# MAIN.net
KiCad netlist of a schematic drawn in Altium Designer
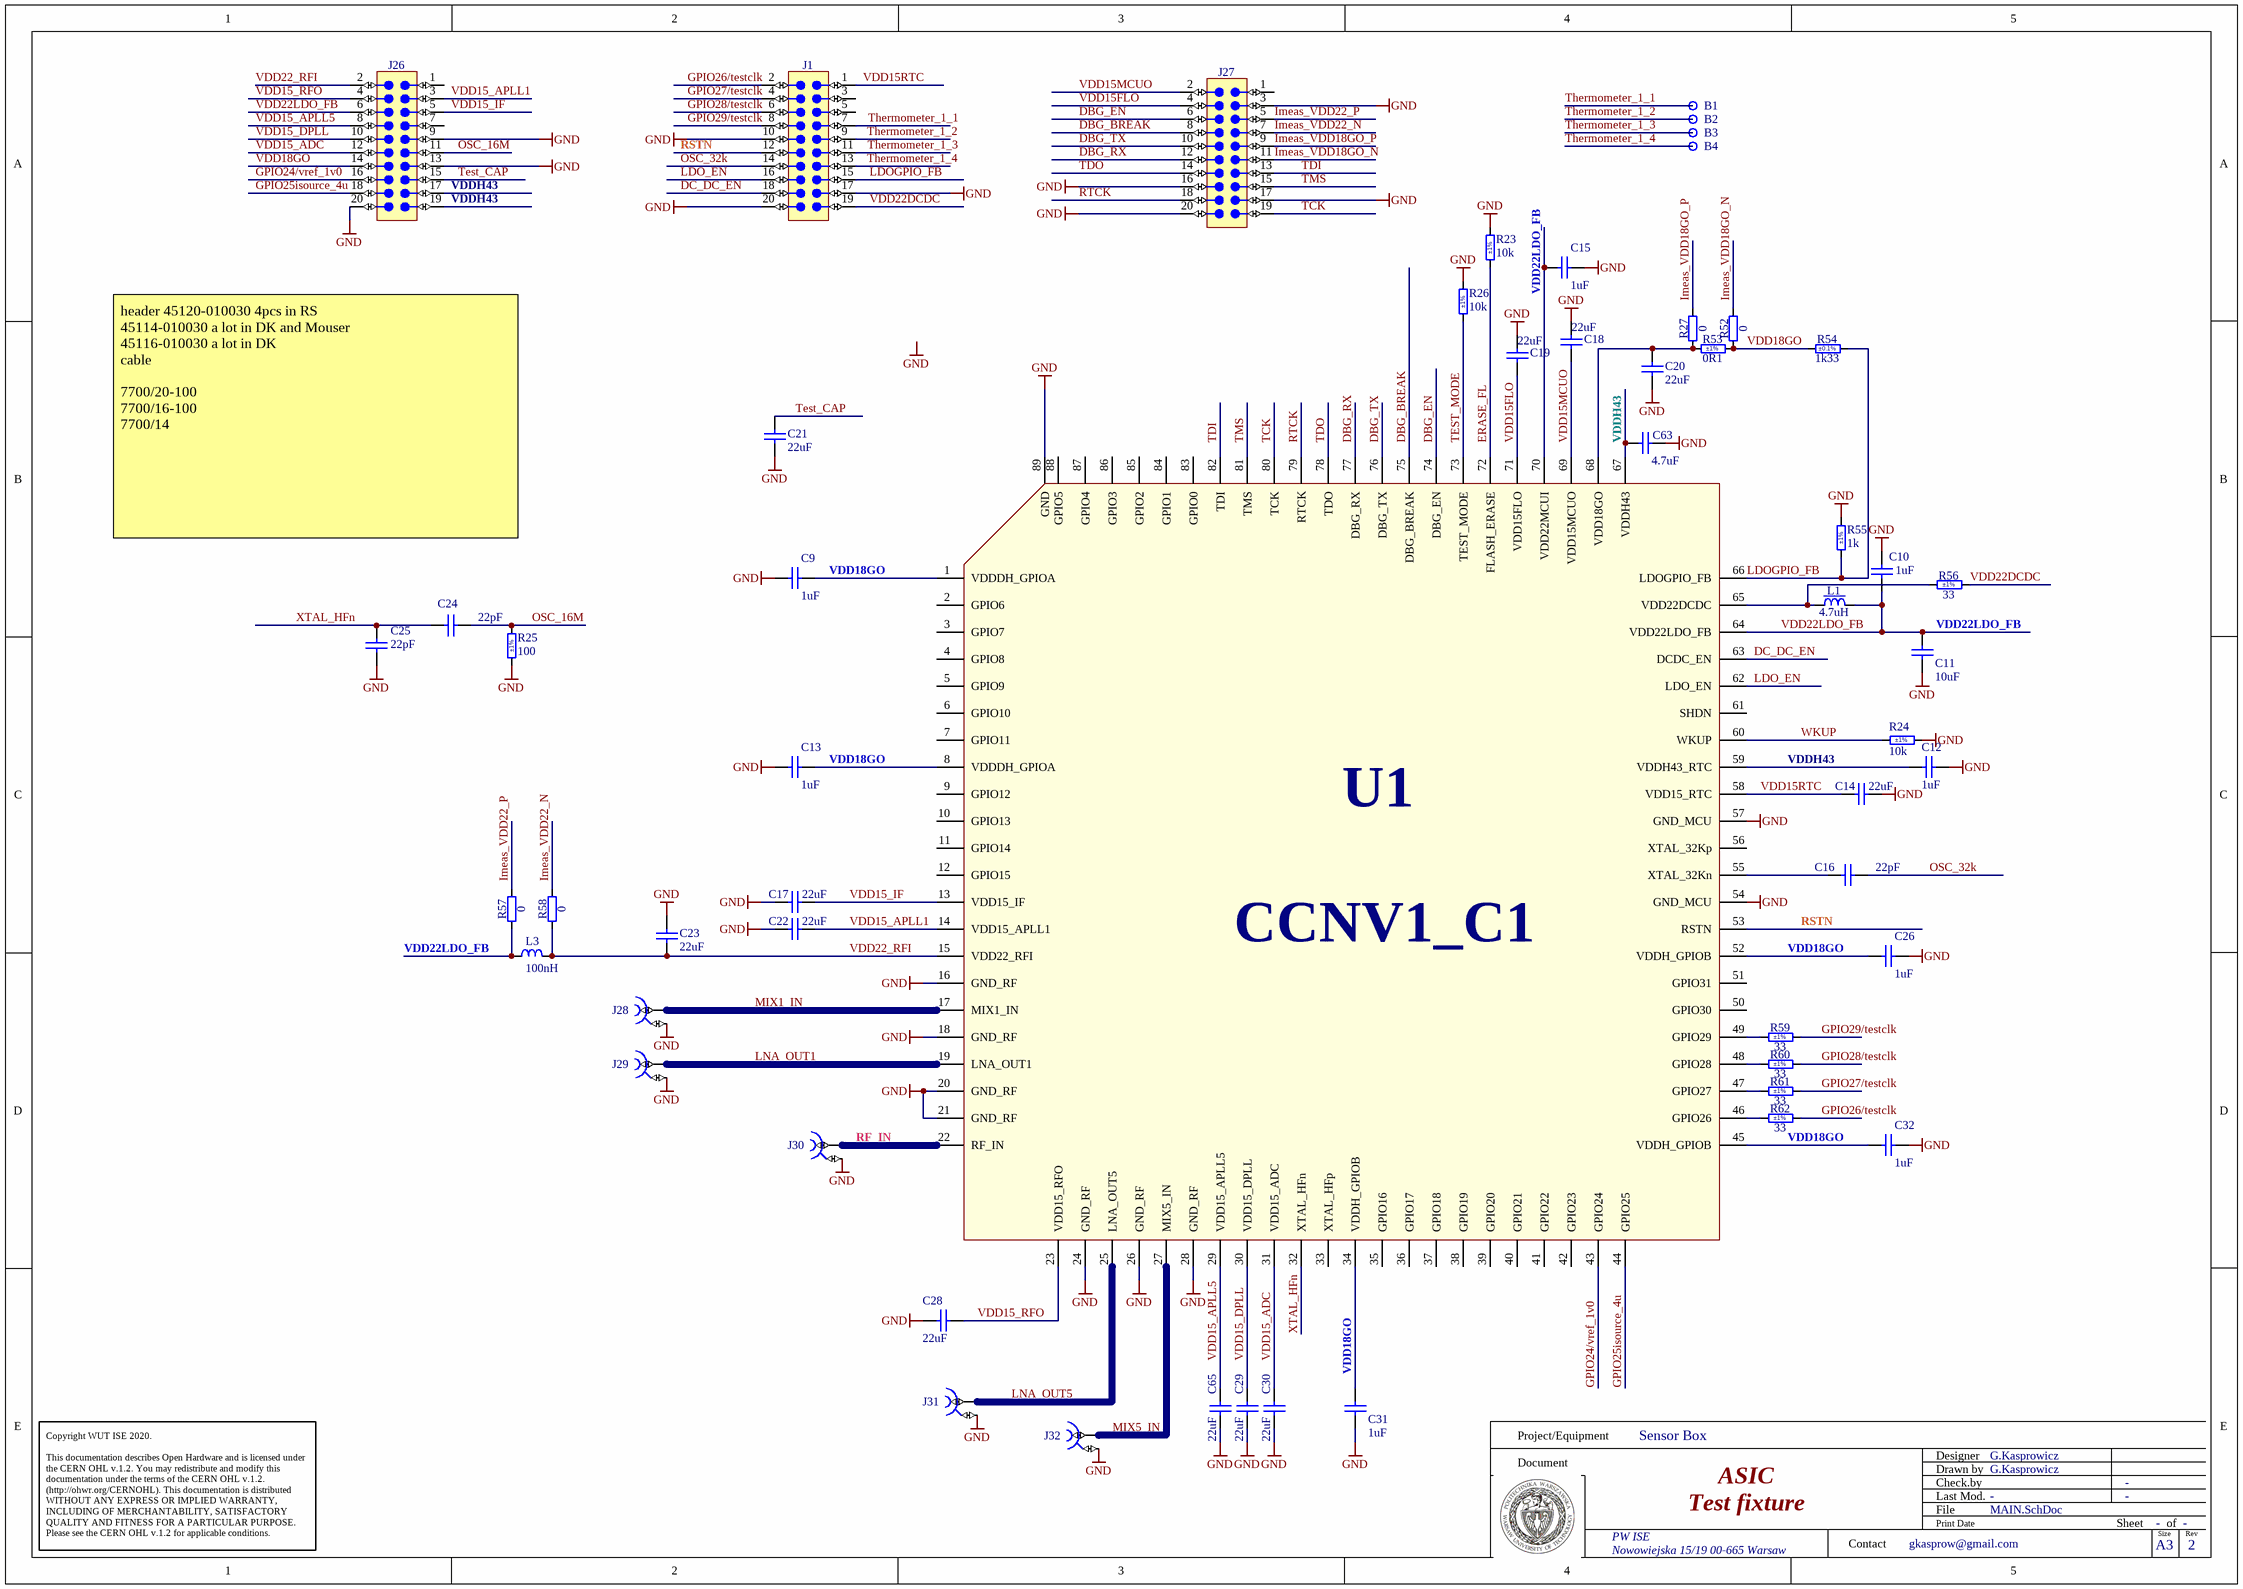
[diagram p0: MAIN.SchDoc]

(export (version "E")
  (design (tool "Eeschema 10.0.6"))
  (components
    (comp (ref "B1")
      (value "Plated Hole")
      (footprint "c100h50")
      (description "Single Terminal Socket")
      (fields (field (name "PART NUMBER") "PLATED_HOLE0.5_PAD1.0") (field (name "AUTHOR") "CERN DEM JMW"))
      (libsource (lib "Eletro-mechanical") (part "Single Terminal Socket"))
    )
    (comp (ref "B2")
      (value "Plated Hole")
      (footprint "c100h50")
      (description "Single Terminal Socket")
      (fields (field (name "PART NUMBER") "PLATED_HOLE0.5_PAD1.0") (field (name "AUTHOR") "CERN DEM JMW"))
      (libsource (lib "Eletro-mechanical") (part "Single Terminal Socket"))
    )
    (comp (ref "B3")
      (value "Plated Hole")
      (footprint "c100h50")
      (description "Single Terminal Socket")
      (fields (field (name "PART NUMBER") "PLATED_HOLE0.5_PAD1.0") (field (name "AUTHOR") "CERN DEM JMW"))
      (libsource (lib "Eletro-mechanical") (part "Single Terminal Socket"))
    )
    (comp (ref "B4")
      (value "Plated Hole")
      (footprint "c100h50")
      (description "Single Terminal Socket")
      (fields (field (name "PART NUMBER") "PLATED_HOLE0.5_PAD1.0") (field (name "AUTHOR") "CERN DEM JMW"))
      (libsource (lib "Eletro-mechanical") (part "Single Terminal Socket"))
    )
    (comp (ref "C9")
      (value "1uF")
      (footprint "CAPC1005X55N")
      (description "Non-polarised capacitor")
      (fields
        (field (name "PART NUMBER") "CC0402_1UF_16V_10%_X5R")
        (field (name "VOLTAGE") "16V")
        (field (name "AUTHOR") "CERN DEM JLC")
      )
      (libsource (lib "Capacitors") (part "Capacitor - non polarized"))
    )
    (comp (ref "C10")
      (value "1uF")
      (footprint "CAPC1005X55N")
      (description "Non-polarised capacitor")
      (fields
        (field (name "PART NUMBER") "CC0402_1UF_16V_10%_X5R")
        (field (name "VOLTAGE") "16V")
        (field (name "AUTHOR") "CERN DEM JLC")
      )
      (libsource (lib "Capacitors") (part "Capacitor - non polarized"))
    )
    (comp (ref "C11")
      (value "10uF")
      (footprint "CAPC1608X80N")
      (description "Non-polarised capacitor")
      (fields
        (field (name "PART NUMBER") "CC0603_10UF_10V_10%_X5R")
        (field (name "VOLTAGE") "10V")
        (field (name "AUTHOR") "CERN DEM JLC")
      )
      (libsource (lib "Capacitors") (part "Capacitor - non polarized"))
    )
    (comp (ref "C12")
      (value "1uF")
      (footprint "CAPC1005X55N")
      (description "Non-polarised capacitor")
      (fields
        (field (name "PART NUMBER") "CC0402_1UF_16V_10%_X5R")
        (field (name "VOLTAGE") "16V")
        (field (name "AUTHOR") "CERN DEM JLC")
      )
      (libsource (lib "Capacitors") (part "Capacitor - non polarized"))
    )
    (comp (ref "C13")
      (value "1uF")
      (footprint "CAPC1005X55N")
      (description "Non-polarised capacitor")
      (fields
        (field (name "PART NUMBER") "CC0402_1UF_16V_10%_X5R")
        (field (name "VOLTAGE") "16V")
        (field (name "AUTHOR") "CERN DEM JLC")
      )
      (libsource (lib "Capacitors") (part "Capacitor - non polarized"))
    )
    (comp (ref "C14")
      (value "22uF")
      (footprint "CAPC1608X90N")
      (description "Non-polarised capacitor")
      (fields
        (field (name "PART NUMBER") "CC0603_22UF_10V_20%_X5R")
        (field (name "VOLTAGE") "10V")
        (field (name "AUTHOR") "CERN DEM BC")
      )
      (libsource (lib "Capacitors") (part "Capacitor - non polarized"))
    )
    (comp (ref "C15")
      (value "1uF")
      (footprint "CAPC1005X55N")
      (description "Non-polarised capacitor")
      (fields
        (field (name "PART NUMBER") "CC0402_1UF_16V_10%_X5R")
        (field (name "VOLTAGE") "16V")
        (field (name "AUTHOR") "CERN DEM JLC")
      )
      (libsource (lib "Capacitors") (part "Capacitor - non polarized"))
    )
    (comp (ref "C16")
      (value "22pF")
      (footprint "CAPC1005X55N")
      (description "Non-polarised capacitor")
      (fields
        (field (name "PART NUMBER") "CC0402_22PF_50V_5%_C0G")
        (field (name "VOLTAGE") "50V")
        (field (name "AUTHOR") "CERN DEM JLC")
      )
      (libsource (lib "Capacitors") (part "Capacitor - non polarized"))
    )
    (comp (ref "C17")
      (value "22uF")
      (footprint "CAPC1608X90N")
      (description "Non-polarised capacitor")
      (fields
        (field (name "PART NUMBER") "CC0603_22UF_10V_20%_X5R")
        (field (name "VOLTAGE") "10V")
        (field (name "AUTHOR") "CERN DEM BC")
      )
      (libsource (lib "Capacitors") (part "Capacitor - non polarized"))
    )
    (comp (ref "C18")
      (value "22uF")
      (footprint "CAPC1608X90N")
      (description "Non-polarised capacitor")
      (fields
        (field (name "PART NUMBER") "CC0603_22UF_10V_20%_X5R")
        (field (name "VOLTAGE") "10V")
        (field (name "AUTHOR") "CERN DEM BC")
      )
      (libsource (lib "Capacitors") (part "Capacitor - non polarized"))
    )
    (comp (ref "C19")
      (value "22uF")
      (footprint "CAPC1608X90N")
      (description "Non-polarised capacitor")
      (fields
        (field (name "PART NUMBER") "CC0603_22UF_10V_20%_X5R")
        (field (name "VOLTAGE") "10V")
        (field (name "AUTHOR") "CERN DEM BC")
      )
      (libsource (lib "Capacitors") (part "Capacitor - non polarized"))
    )
    (comp (ref "C20")
      (value "22uF")
      (footprint "CAPC1608X90N")
      (description "Non-polarised capacitor")
      (fields
        (field (name "PART NUMBER") "CC0603_22UF_10V_20%_X5R")
        (field (name "VOLTAGE") "10V")
        (field (name "AUTHOR") "CERN DEM BC")
      )
      (libsource (lib "Capacitors") (part "Capacitor - non polarized"))
    )
    (comp (ref "C21")
      (value "22uF")
      (footprint "CAPC1608X90N")
      (description "Non-polarised capacitor")
      (fields
        (field (name "PART NUMBER") "CC0603_22UF_10V_20%_X5R")
        (field (name "VOLTAGE") "10V")
        (field (name "AUTHOR") "CERN DEM BC")
      )
      (libsource (lib "Capacitors") (part "Capacitor - non polarized"))
    )
    (comp (ref "C22")
      (value "22uF")
      (footprint "CAPC1608X90N")
      (description "Non-polarised capacitor")
      (fields
        (field (name "PART NUMBER") "CC0603_22UF_10V_20%_X5R")
        (field (name "VOLTAGE") "10V")
        (field (name "AUTHOR") "CERN DEM BC")
      )
      (libsource (lib "Capacitors") (part "Capacitor - non polarized"))
    )
    (comp (ref "C23")
      (value "22uF")
      (footprint "CAPC1608X90N")
      (description "Non-polarised capacitor")
      (fields
        (field (name "PART NUMBER") "CC0603_22UF_10V_20%_X5R")
        (field (name "VOLTAGE") "10V")
        (field (name "AUTHOR") "CERN DEM BC")
      )
      (libsource (lib "Capacitors") (part "Capacitor - non polarized"))
    )
    (comp (ref "C24")
      (value "22pF")
      (footprint "CAPC1005X55N")
      (description "Non-polarised capacitor")
      (fields
        (field (name "PART NUMBER") "CC0402_22PF_50V_5%_C0G")
        (field (name "VOLTAGE") "50V")
        (field (name "AUTHOR") "CERN DEM JLC")
      )
      (libsource (lib "Capacitors") (part "Capacitor - non polarized"))
    )
    (comp (ref "C25")
      (value "22pF")
      (footprint "CAPC1005X55N")
      (description "Non-polarised capacitor")
      (fields
        (field (name "PART NUMBER") "CC0402_22PF_50V_5%_C0G")
        (field (name "VOLTAGE") "50V")
        (field (name "AUTHOR") "CERN DEM JLC")
      )
      (libsource (lib "Capacitors") (part "Capacitor - non polarized"))
    )
    (comp (ref "C26")
      (value "1uF")
      (footprint "CAPC1005X55N")
      (description "Non-polarised capacitor")
      (fields
        (field (name "PART NUMBER") "CC0402_1UF_16V_10%_X5R")
        (field (name "VOLTAGE") "16V")
        (field (name "AUTHOR") "CERN DEM JLC")
      )
      (libsource (lib "Capacitors") (part "Capacitor - non polarized"))
    )
    (comp (ref "C28")
      (value "22uF")
      (footprint "CAPC1608X90N")
      (description "Non-polarised capacitor")
      (fields
        (field (name "PART NUMBER") "CC0603_22UF_10V_20%_X5R")
        (field (name "VOLTAGE") "10V")
        (field (name "AUTHOR") "CERN DEM BC")
      )
      (libsource (lib "Capacitors") (part "Capacitor - non polarized"))
    )
    (comp (ref "C29")
      (value "22uF")
      (footprint "CAPC1608X90N")
      (description "Non-polarised capacitor")
      (fields
        (field (name "PART NUMBER") "CC0603_22UF_10V_20%_X5R")
        (field (name "VOLTAGE") "10V")
        (field (name "AUTHOR") "CERN DEM BC")
      )
      (libsource (lib "Capacitors") (part "Capacitor - non polarized"))
    )
    (comp (ref "C30")
      (value "22uF")
      (footprint "CAPC1608X90N")
      (description "Non-polarised capacitor")
      (fields
        (field (name "PART NUMBER") "CC0603_22UF_10V_20%_X5R")
        (field (name "VOLTAGE") "10V")
        (field (name "AUTHOR") "CERN DEM BC")
      )
      (libsource (lib "Capacitors") (part "Capacitor - non polarized"))
    )
    (comp (ref "C31")
      (value "1uF")
      (footprint "CAPC1005X55N")
      (description "Non-polarised capacitor")
      (fields
        (field (name "PART NUMBER") "CC0402_1UF_16V_10%_X5R")
        (field (name "VOLTAGE") "16V")
        (field (name "AUTHOR") "CERN DEM JLC")
      )
      (libsource (lib "Capacitors") (part "Capacitor - non polarized"))
    )
    (comp (ref "C32")
      (value "1uF")
      (footprint "CAPC1005X55N")
      (description "Non-polarised capacitor")
      (fields
        (field (name "PART NUMBER") "CC0402_1UF_16V_10%_X5R")
        (field (name "VOLTAGE") "16V")
        (field (name "AUTHOR") "CERN DEM JLC")
      )
      (libsource (lib "Capacitors") (part "Capacitor - non polarized"))
    )
    (comp (ref "C63")
      (value "4.7uF")
      (footprint "CAPC1005X55N")
      (description "Non-polarised capacitor")
      (fields
        (field (name "PART NUMBER") "CC0402_4.7UF_10V_10%_X5R")
        (field (name "VOLTAGE") "10V")
        (field (name "AUTHOR") "CERN DEM BC")
      )
      (libsource (lib "Capacitors") (part "Capacitor - non polarized"))
    )
    (comp (ref "C65")
      (value "22uF")
      (footprint "CAPC1608X90N")
      (description "Non-polarised capacitor")
      (fields
        (field (name "PART NUMBER") "CC0603_22UF_10V_20%_X5R")
        (field (name "VOLTAGE") "10V")
        (field (name "AUTHOR") "CERN DEM BC")
      )
      (libsource (lib "Capacitors") (part "Capacitor - non polarized"))
    )
    (comp (ref "J1")
      (value "Header 20")
      (footprint "3M_45220-600230")
      (description "Connector 20 Male")
      (fields
        (field (name "PART NUMBER") "3M_45220-600230")
        (field (name "MANUFACTURER") "3M")
        (field (name "AUTHOR") "CERN DEM MR")
      )
      (libsource (lib "Connectors") (part "Connector 20 Male"))
    )
    (comp (ref "J26")
      (value "Header 20")
      (footprint "3M_45220-600230")
      (description "Connector 20 Male")
      (fields
        (field (name "PART NUMBER") "3M_45220-600230")
        (field (name "MANUFACTURER") "3M")
        (field (name "AUTHOR") "CERN DEM MR")
      )
      (libsource (lib "Connectors") (part "Connector 20 Male"))
    )
    (comp (ref "J27")
      (value "Header 20")
      (footprint "3M_45220-600230")
      (description "Connector 20 Male")
      (fields
        (field (name "PART NUMBER") "3M_45220-600230")
        (field (name "MANUFACTURER") "3M")
        (field (name "AUTHOR") "CERN DEM MR")
      )
      (libsource (lib "Connectors") (part "Connector 20 Male"))
    )
    (comp (ref "J28")
      (value "Coax_1Female_1Shield")
      (footprint "SAMTEC_MMCX-J-P-H-ST-TH1")
      (fields
        (field (name "PART NUMBER") "SAMTEC_MMCX-J-P-H-ST-TH1")
        (field (name "MANUFACTURER") "SAMTEC")
        (field (name "MANUFACTURER PART NUMBER") "MMCX-J-P-H-ST-TH1")
        (field (name "AUTHOR") "CERN DEM JLC")
      )
      (libsource (lib "Connectors") (part "Coax_1Female_1Shield"))
    )
    (comp (ref "J29")
      (value "Coax_1Female_1Shield")
      (footprint "SAMTEC_MMCX-J-P-H-ST-TH1")
      (fields
        (field (name "PART NUMBER") "SAMTEC_MMCX-J-P-H-ST-TH1")
        (field (name "MANUFACTURER") "SAMTEC")
        (field (name "MANUFACTURER PART NUMBER") "MMCX-J-P-H-ST-TH1")
        (field (name "AUTHOR") "CERN DEM JLC")
      )
      (libsource (lib "Connectors") (part "Coax_1Female_1Shield"))
    )
    (comp (ref "J30")
      (value "Coax_1Female_1Shield")
      (footprint "SAMTEC_MMCX-J-P-H-ST-TH1")
      (fields
        (field (name "PART NUMBER") "SAMTEC_MMCX-J-P-H-ST-TH1")
        (field (name "MANUFACTURER") "SAMTEC")
        (field (name "MANUFACTURER PART NUMBER") "MMCX-J-P-H-ST-TH1")
        (field (name "AUTHOR") "CERN DEM JLC")
      )
      (libsource (lib "Connectors") (part "Coax_1Female_1Shield"))
    )
    (comp (ref "J31")
      (value "Coax_1Female_1Shield")
      (footprint "SAMTEC_MMCX-J-P-H-ST-TH1")
      (fields
        (field (name "PART NUMBER") "SAMTEC_MMCX-J-P-H-ST-TH1")
        (field (name "MANUFACTURER") "SAMTEC")
        (field (name "MANUFACTURER PART NUMBER") "MMCX-J-P-H-ST-TH1")
        (field (name "AUTHOR") "CERN DEM JLC")
      )
      (libsource (lib "Connectors") (part "Coax_1Female_1Shield"))
    )
    (comp (ref "J32")
      (value "Coax_1Female_1Shield")
      (footprint "SAMTEC_MMCX-J-P-H-ST-TH1")
      (fields
        (field (name "PART NUMBER") "SAMTEC_MMCX-J-P-H-ST-TH1")
        (field (name "MANUFACTURER") "SAMTEC")
        (field (name "MANUFACTURER PART NUMBER") "MMCX-J-P-H-ST-TH1")
        (field (name "AUTHOR") "CERN DEM JLC")
      )
      (libsource (lib "Connectors") (part "Coax_1Female_1Shield"))
    )
    (comp (ref "L1")
      (value "4.7uH")
      (footprint "INDC2012X145N")
      (description "Inductor With Core")
      (fields
        (field (name "PART NUMBER") "IND0805_4.7UH_20%_KEMET_L-DWI")
        (field (name "POWER") "360mA")
        (field (name "AUTHOR") "CERN DEM JLC")
      )
      (libsource (lib "Inductors & Transformers") (part "Inductor With Magnetic core"))
    )
    (comp (ref "L3")
      (value "100nH")
      (footprint "INDC1005X55N")
      (description "Inductor")
      (fields
        (field (name "PART NUMBER") "IND0402_100NH_5%_TDK_MLJ1005")
        (field (name "POWER") "400mA")
        (field (name "AUTHOR") "CERN DEM BC")
      )
      (libsource (lib "Inductors & Transformers") (part "Inductor"))
    )
    (comp (ref "R23")
      (value "10k")
      (footprint "RESC1005X40N")
      (description "Resistor - 1%")
      (fields
        (field (name "TOLERANCE") "±1%")
        (field (name "PART NUMBER") "R0402_10K_1%_0.0625W_100PPM")
        (field (name "POWER") "0.0625W")
        (field (name "AUTHOR") "CERN DEM JLC")
      )
      (libsource (lib "Resistors") (part "Resistor - 1%"))
    )
    (comp (ref "R24")
      (value "10k")
      (footprint "RESC1005X40N")
      (description "Resistor - 1%")
      (fields
        (field (name "TOLERANCE") "±1%")
        (field (name "PART NUMBER") "R0402_10K_1%_0.0625W_100PPM")
        (field (name "POWER") "0.0625W")
        (field (name "AUTHOR") "CERN DEM JLC")
      )
      (libsource (lib "Resistors") (part "Resistor - 1%"))
    )
    (comp (ref "R25")
      (value "100")
      (footprint "RESC1005X40N")
      (description "Resistor - 1%")
      (fields
        (field (name "TOLERANCE") "±1%")
        (field (name "PART NUMBER") "R0402_100R_1%_0.0625W_100PPM")
        (field (name "POWER") "0.0625W")
        (field (name "AUTHOR") "CERN DEM JLC")
      )
      (libsource (lib "Resistors") (part "Resistor - 1%"))
    )
    (comp (ref "R26")
      (value "10k")
      (footprint "RESC1005X40N")
      (description "Resistor - 1%")
      (fields
        (field (name "TOLERANCE") "±1%")
        (field (name "PART NUMBER") "R0402_10K_1%_0.0625W_100PPM")
        (field (name "POWER") "0.0625W")
        (field (name "AUTHOR") "CERN DEM JLC")
      )
      (libsource (lib "Resistors") (part "Resistor - 1%"))
    )
    (comp (ref "R27")
      (value "0")
      (footprint "RESC1005X40N")
      (description "Resistor")
      (fields
        (field (name "PART NUMBER") "R0402_0R_JUMPER")
        (field (name "MANUFACTURER") "GENERIC")
        (field (name "AUTHOR") "CERN DEM JLC")
      )
      (libsource (lib "Resistors") (part "Resistor"))
    )
    (comp (ref "R52")
      (value "0")
      (footprint "RESC1005X40N")
      (description "Resistor")
      (fields
        (field (name "PART NUMBER") "R0402_0R_JUMPER")
        (field (name "MANUFACTURER") "GENERIC")
        (field (name "AUTHOR") "CERN DEM JLC")
      )
      (libsource (lib "Resistors") (part "Resistor"))
    )
    (comp (ref "R53")
      (value "0R1")
      (footprint "RESC1608X55N")
      (description "Resistor - 1%")
      (fields
        (field (name "TOLERANCE") "±1%")
        (field (name "PART NUMBER") "R0603_0R1_1%_0.1W_200PPM")
        (field (name "POWER") "0.1W")
        (field (name "AUTHOR") "CERN DEM JMW")
      )
      (libsource (lib "Resistors") (part "Resistor - 1%"))
    )
    (comp (ref "R54")
      (value "1k33")
      (footprint "RESC1608X55N")
      (description "Resistor - 0.1%")
      (fields
        (field (name "TOLERANCE") "±0.1%")
        (field (name "PART NUMBER") "R0603_1K33_0.1%_0.063W_10PPM")
        (field (name "POWER") "0.063W")
        (field (name "AUTHOR") "CERN DEM JLC")
      )
      (libsource (lib "Resistors") (part "Resistor - 0.1%"))
    )
    (comp (ref "R55")
      (value "1k")
      (footprint "RESC1005X40N")
      (description "Resistor - 1%")
      (fields
        (field (name "TOLERANCE") "±1%")
        (field (name "PART NUMBER") "R0402_1K_1%_0.0625W_100PPM")
        (field (name "POWER") "0.0625W")
        (field (name "AUTHOR") "CERN DEM JLC")
      )
      (libsource (lib "Resistors") (part "Resistor - 1%"))
    )
    (comp (ref "R56")
      (value "33")
      (footprint "RESC1005X40N")
      (description "Resistor - 1%")
      (fields
        (field (name "TOLERANCE") "±1%")
        (field (name "PART NUMBER") "R0402_33R_1%_0.0625W_100PPM")
        (field (name "POWER") "0.0625W")
        (field (name "AUTHOR") "CERN DEM JLC")
      )
      (libsource (lib "Resistors") (part "Resistor - 1%"))
    )
    (comp (ref "R57")
      (value "0")
      (footprint "RESC1005X40N")
      (description "Resistor")
      (fields
        (field (name "PART NUMBER") "R0402_0R_JUMPER")
        (field (name "MANUFACTURER") "GENERIC")
        (field (name "AUTHOR") "CERN DEM JLC")
      )
      (libsource (lib "Resistors") (part "Resistor"))
    )
    (comp (ref "R58")
      (value "0")
      (footprint "RESC1005X40N")
      (description "Resistor")
      (fields
        (field (name "PART NUMBER") "R0402_0R_JUMPER")
        (field (name "MANUFACTURER") "GENERIC")
        (field (name "AUTHOR") "CERN DEM JLC")
      )
      (libsource (lib "Resistors") (part "Resistor"))
    )
    (comp (ref "R59")
      (value "33")
      (footprint "RESC1005X40N")
      (description "Resistor - 1%")
      (fields
        (field (name "TOLERANCE") "±1%")
        (field (name "PART NUMBER") "R0402_33R_1%_0.0625W_100PPM")
        (field (name "POWER") "0.0625W")
        (field (name "AUTHOR") "CERN DEM JLC")
      )
      (libsource (lib "Resistors") (part "Resistor - 1%"))
    )
    (comp (ref "R60")
      (value "33")
      (footprint "RESC1005X40N")
      (description "Resistor - 1%")
      (fields
        (field (name "TOLERANCE") "±1%")
        (field (name "PART NUMBER") "R0402_33R_1%_0.0625W_100PPM")
        (field (name "POWER") "0.0625W")
        (field (name "AUTHOR") "CERN DEM JLC")
      )
      (libsource (lib "Resistors") (part "Resistor - 1%"))
    )
    (comp (ref "R61")
      (value "33")
      (footprint "RESC1005X40N")
      (description "Resistor - 1%")
      (fields
        (field (name "TOLERANCE") "±1%")
        (field (name "PART NUMBER") "R0402_33R_1%_0.0625W_100PPM")
        (field (name "POWER") "0.0625W")
        (field (name "AUTHOR") "CERN DEM JLC")
      )
      (libsource (lib "Resistors") (part "Resistor - 1%"))
    )
    (comp (ref "R62")
      (value "33")
      (footprint "RESC1005X40N")
      (description "Resistor - 1%")
      (fields
        (field (name "TOLERANCE") "±1%")
        (field (name "PART NUMBER") "R0402_33R_1%_0.0625W_100PPM")
        (field (name "POWER") "0.0625W")
        (field (name "AUTHOR") "CERN DEM JLC")
      )
      (libsource (lib "Resistors") (part "Resistor - 1%"))
    )
    (comp (ref "U1")
      (value "CCNV1_C1")
      (footprint "QFN88-0,4(10x10) - podstawka 2")
      (description "Układ scalony")
      (libsource (lib "CCNV1_C1") (part "CCNV1_C1"))
    )
  )
  (nets
    (net (code "1") (name "/DBG_BREAK") (class "Default")
      (node (ref "J27") (pin "8") (pinfunction "8_8") (pintype "bidirectional"))
      (node (ref "U1") (pin "75") (pinfunction "DBG_BREAK_75") (pintype "passive"))
    )
    (net (code "2") (name "/DBG_EN") (class "Default")
      (node (ref "J27") (pin "6") (pinfunction "6_6") (pintype "bidirectional"))
      (node (ref "U1") (pin "74") (pinfunction "DBG_EN_74") (pintype "passive"))
    )
    (net (code "3") (name "/DBG_RX") (class "Default")
      (node (ref "J27") (pin "12") (pinfunction "12_12") (pintype "bidirectional"))
      (node (ref "U1") (pin "77") (pinfunction "DBG_RX_77") (pintype "passive"))
    )
    (net (code "4") (name "/DBG_TX") (class "Default")
      (node (ref "J27") (pin "10") (pinfunction "10_10") (pintype "bidirectional"))
      (node (ref "U1") (pin "76") (pinfunction "DBG_TX_76") (pintype "passive"))
    )
    (net (code "5") (name "/DC_DC_EN") (class "Default")
      (node (ref "J1") (pin "18") (pinfunction "18_18") (pintype "bidirectional"))
      (node (ref "U1") (pin "63") (pinfunction "DCDC_EN_63") (pintype "passive"))
    )
    (net (code "6") (name "/ERASE_FL") (class "Default")
      (node (ref "R23") (pin "1") (pinfunction "1_1") (pintype "passive"))
      (node (ref "U1") (pin "72") (pinfunction "FLASH_ERASE_72") (pintype "passive"))
    )
    (net (code "7") (name "/GPIO24{slash}vref_1v0") (class "Default")
      (node (ref "J26") (pin "16") (pinfunction "16_16") (pintype "bidirectional"))
      (node (ref "U1") (pin "43") (pinfunction "GPIO24_43") (pintype "passive"))
    )
    (net (code "8") (name "/GPIO25isource_4u") (class "Default")
      (node (ref "J26") (pin "18") (pinfunction "18_18") (pintype "bidirectional"))
      (node (ref "U1") (pin "44") (pinfunction "GPIO25_44") (pintype "passive"))
    )
    (net (code "9") (name "/GPIO26{slash}testclk") (class "Default")
      (node (ref "J1") (pin "2") (pinfunction "2_2") (pintype "bidirectional"))
      (node (ref "R62") (pin "2") (pinfunction "2_2") (pintype "passive"))
    )
    (net (code "10") (name "/GPIO27{slash}testclk") (class "Default")
      (node (ref "J1") (pin "4") (pinfunction "4_4") (pintype "bidirectional"))
      (node (ref "R61") (pin "2") (pinfunction "2_2") (pintype "passive"))
    )
    (net (code "11") (name "/GPIO28{slash}testclk") (class "Default")
      (node (ref "J1") (pin "6") (pinfunction "6_6") (pintype "bidirectional"))
      (node (ref "R60") (pin "2") (pinfunction "2_2") (pintype "passive"))
    )
    (net (code "12") (name "/GPIO29{slash}testclk") (class "Default")
      (node (ref "J1") (pin "8") (pinfunction "8_8") (pintype "bidirectional"))
      (node (ref "R59") (pin "2") (pinfunction "2_2") (pintype "passive"))
    )
    (net (code "13") (name "/Imeas_VDD18GO_N") (class "Default")
      (node (ref "J27") (pin "11") (pinfunction "11_11") (pintype "bidirectional"))
      (node (ref "R52") (pin "2") (pinfunction "2_2") (pintype "passive"))
    )
    (net (code "14") (name "/Imeas_VDD18GO_P") (class "Default")
      (node (ref "J27") (pin "9") (pinfunction "9_9") (pintype "bidirectional"))
      (node (ref "R27") (pin "2") (pinfunction "2_2") (pintype "passive"))
    )
    (net (code "15") (name "/Imeas_VDD22_N") (class "Default")
      (node (ref "J27") (pin "7") (pinfunction "7_7") (pintype "bidirectional"))
      (node (ref "R58") (pin "2") (pinfunction "2_2") (pintype "passive"))
    )
    (net (code "16") (name "/Imeas_VDD22_P") (class "Default")
      (node (ref "J27") (pin "5") (pinfunction "5_5") (pintype "bidirectional"))
      (node (ref "R57") (pin "2") (pinfunction "2_2") (pintype "passive"))
    )
    (net (code "17") (name "/LDOGPIO_FB") (class "Default")
      (node (ref "J1") (pin "15") (pinfunction "15_15") (pintype "bidirectional"))
      (node (ref "R54") (pin "2") (pinfunction "2_2") (pintype "passive"))
      (node (ref "R55") (pin "1") (pinfunction "1_1") (pintype "passive"))
      (node (ref "U1") (pin "66") (pinfunction "LDOGPIO_FB_66") (pintype "passive"))
    )
    (net (code "18") (name "/LDO_EN") (class "Default")
      (node (ref "J1") (pin "16") (pinfunction "16_16") (pintype "bidirectional"))
      (node (ref "U1") (pin "62") (pinfunction "LDO_EN_62") (pintype "passive"))
    )
    (net (code "19") (name "/LNA_OUT1") (class "Default")
      (node (ref "J29") (pin "1") (pinfunction "1_1") (pintype "bidirectional"))
      (node (ref "U1") (pin "19") (pinfunction "LNA_OUT1_19") (pintype "passive"))
    )
    (net (code "20") (name "/LNA_OUT5") (class "Default")
      (node (ref "J31") (pin "1") (pinfunction "1_1") (pintype "bidirectional"))
      (node (ref "U1") (pin "25") (pinfunction "LNA_OUT5_25") (pintype "passive"))
    )
    (net (code "21") (name "/MIX1_IN") (class "Default")
      (node (ref "J28") (pin "1") (pinfunction "1_1") (pintype "bidirectional"))
      (node (ref "U1") (pin "17") (pinfunction "MIX1_IN_17") (pintype "passive"))
    )
    (net (code "22") (name "/MIX5_IN") (class "Default")
      (node (ref "J32") (pin "1") (pinfunction "1_1") (pintype "bidirectional"))
      (node (ref "U1") (pin "27") (pinfunction "MIX5_IN_27") (pintype "passive"))
    )
    (net (code "23") (name "/OSC_16M") (class "Default")
      (node (ref "C24") (pin "1") (pinfunction "1_1") (pintype "passive"))
      (node (ref "J26") (pin "11") (pinfunction "11_11") (pintype "bidirectional"))
      (node (ref "R25") (pin "2") (pinfunction "2_2") (pintype "passive"))
    )
    (net (code "24") (name "/OSC_32k") (class "Default")
      (node (ref "C16") (pin "1") (pinfunction "1_1") (pintype "passive"))
      (node (ref "J1") (pin "14") (pinfunction "14_14") (pintype "bidirectional"))
    )
    (net (code "25") (name "/RF_IN") (class "Default")
      (node (ref "J30") (pin "1") (pinfunction "1_1") (pintype "bidirectional"))
      (node (ref "U1") (pin "22") (pinfunction "RF_IN_22") (pintype "passive"))
    )
    (net (code "26") (name "/RSTN") (class "Default")
      (node (ref "J1") (pin "12") (pinfunction "12_12") (pintype "bidirectional"))
      (node (ref "U1") (pin "53") (pinfunction "RSTN_53") (pintype "passive"))
    )
    (net (code "27") (name "/RTCK") (class "Default")
      (node (ref "J27") (pin "18") (pinfunction "18_18") (pintype "bidirectional"))
      (node (ref "U1") (pin "79") (pinfunction "RTCK_79") (pintype "passive"))
    )
    (net (code "28") (name "/TCK") (class "Default")
      (node (ref "J27") (pin "19") (pinfunction "19_19") (pintype "bidirectional"))
      (node (ref "U1") (pin "80") (pinfunction "TCK_80") (pintype "passive"))
    )
    (net (code "29") (name "/TDI") (class "Default")
      (node (ref "J27") (pin "13") (pinfunction "13_13") (pintype "bidirectional"))
      (node (ref "U1") (pin "82") (pinfunction "TDI_82") (pintype "passive"))
    )
    (net (code "30") (name "/TDO") (class "Default")
      (node (ref "J27") (pin "14") (pinfunction "14_14") (pintype "bidirectional"))
      (node (ref "U1") (pin "78") (pinfunction "TDO_78") (pintype "passive"))
    )
    (net (code "31") (name "/TEST_MODE") (class "Default")
      (node (ref "R26") (pin "1") (pinfunction "1_1") (pintype "passive"))
      (node (ref "U1") (pin "73") (pinfunction "TEST_MODE_73") (pintype "passive"))
    )
    (net (code "32") (name "/TMS") (class "Default")
      (node (ref "J27") (pin "15") (pinfunction "15_15") (pintype "bidirectional"))
      (node (ref "U1") (pin "81") (pinfunction "TMS_81") (pintype "passive"))
    )
    (net (code "33") (name "/Test_CAP") (class "Default")
      (node (ref "C21") (pin "2") (pinfunction "2_2") (pintype "passive"))
      (node (ref "J26") (pin "15") (pinfunction "15_15") (pintype "bidirectional"))
    )
    (net (code "34") (name "/Thermometer_1_1") (class "Default")
      (node (ref "B1") (pin "1") (pinfunction "1_1") (pintype "bidirectional"))
      (node (ref "J1") (pin "7") (pinfunction "7_7") (pintype "bidirectional"))
    )
    (net (code "35") (name "/Thermometer_1_2") (class "Default")
      (node (ref "B2") (pin "1") (pinfunction "1_1") (pintype "bidirectional"))
      (node (ref "J1") (pin "9") (pinfunction "9_9") (pintype "bidirectional"))
    )
    (net (code "36") (name "/Thermometer_1_3") (class "Default")
      (node (ref "B3") (pin "1") (pinfunction "1_1") (pintype "bidirectional"))
      (node (ref "J1") (pin "11") (pinfunction "11_11") (pintype "bidirectional"))
    )
    (net (code "37") (name "/Thermometer_1_4") (class "Default")
      (node (ref "B4") (pin "1") (pinfunction "1_1") (pintype "bidirectional"))
      (node (ref "J1") (pin "13") (pinfunction "13_13") (pintype "bidirectional"))
    )
    (net (code "38") (name "/VDD15FLO") (class "Default")
      (node (ref "C19") (pin "1") (pinfunction "1_1") (pintype "passive"))
      (node (ref "J27") (pin "4") (pinfunction "4_4") (pintype "bidirectional"))
      (node (ref "U1") (pin "71") (pinfunction "VDD15FLO_71") (pintype "passive"))
    )
    (net (code "39") (name "/VDD15MCUO") (class "Default")
      (node (ref "C18") (pin "1") (pinfunction "1_1") (pintype "passive"))
      (node (ref "J27") (pin "2") (pinfunction "2_2") (pintype "bidirectional"))
      (node (ref "U1") (pin "69") (pinfunction "VDD15MCUO_69") (pintype "passive"))
    )
    (net (code "40") (name "/VDD15RTC") (class "Default")
      (node (ref "C14") (pin "1") (pinfunction "1_1") (pintype "passive"))
      (node (ref "J1") (pin "1") (pinfunction "1_1") (pintype "bidirectional"))
      (node (ref "U1") (pin "58") (pinfunction "VDD15_RTC_58") (pintype "passive"))
    )
    (net (code "41") (name "/VDD15_ADC") (class "Default")
      (node (ref "C30") (pin "2") (pinfunction "2_2") (pintype "passive"))
      (node (ref "J26") (pin "12") (pinfunction "12_12") (pintype "bidirectional"))
      (node (ref "U1") (pin "31") (pinfunction "VDD15_ADC_31") (pintype "passive"))
    )
    (net (code "42") (name "/VDD15_APLL1") (class "Default")
      (node (ref "C22") (pin "2") (pinfunction "2_2") (pintype "passive"))
      (node (ref "J26") (pin "3") (pinfunction "3_3") (pintype "bidirectional"))
      (node (ref "U1") (pin "14") (pinfunction "VDD15_APLL1_14") (pintype "passive"))
    )
    (net (code "43") (name "/VDD15_APLL5") (class "Default")
      (node (ref "C65") (pin "2") (pinfunction "2_2") (pintype "passive"))
      (node (ref "J26") (pin "8") (pinfunction "8_8") (pintype "bidirectional"))
      (node (ref "U1") (pin "29") (pinfunction "VDD15_APLL5_29") (pintype "passive"))
    )
    (net (code "44") (name "/VDD15_DPLL") (class "Default")
      (node (ref "C29") (pin "2") (pinfunction "2_2") (pintype "passive"))
      (node (ref "J26") (pin "10") (pinfunction "10_10") (pintype "bidirectional"))
      (node (ref "U1") (pin "30") (pinfunction "VDD15_DPLL_30") (pintype "passive"))
    )
    (net (code "45") (name "/VDD15_IF") (class "Default")
      (node (ref "C17") (pin "2") (pinfunction "2_2") (pintype "passive"))
      (node (ref "J26") (pin "5") (pinfunction "5_5") (pintype "bidirectional"))
      (node (ref "U1") (pin "13") (pinfunction "VDD15_IF_13") (pintype "passive"))
    )
    (net (code "46") (name "/VDD15_RFO") (class "Default")
      (node (ref "C28") (pin "2") (pinfunction "2_2") (pintype "passive"))
      (node (ref "J26") (pin "4") (pinfunction "4_4") (pintype "bidirectional"))
      (node (ref "U1") (pin "23") (pinfunction "VDD15_RFO_23") (pintype "passive"))
    )
    (net (code "47") (name "/VDD18GO") (class "Default")
      (node (ref "C13") (pin "1") (pinfunction "1_1") (pintype "passive"))
      (node (ref "C26") (pin "2") (pinfunction "2_2") (pintype "passive"))
      (node (ref "C31") (pin "2") (pinfunction "2_2") (pintype "passive"))
      (node (ref "C32") (pin "2") (pinfunction "2_2") (pintype "passive"))
      (node (ref "C9") (pin "1") (pinfunction "1_1") (pintype "passive"))
      (node (ref "J26") (pin "14") (pinfunction "14_14") (pintype "bidirectional"))
      (node (ref "R52") (pin "1") (pinfunction "1_1") (pintype "passive"))
      (node (ref "R53") (pin "2") (pinfunction "2_2") (pintype "passive"))
      (node (ref "R54") (pin "1") (pinfunction "1_1") (pintype "passive"))
      (node (ref "U1") (pin "1") (pinfunction "VDDDH_GPIOA_1") (pintype "passive"))
      (node (ref "U1") (pin "34") (pinfunction "VDDH_GPIOB_34") (pintype "passive"))
      (node (ref "U1") (pin "45") (pinfunction "VDDH_GPIOB_45") (pintype "passive"))
      (node (ref "U1") (pin "52") (pinfunction "VDDH_GPIOB_52") (pintype "passive"))
      (node (ref "U1") (pin "8") (pinfunction "VDDDH_GPIOA_8") (pintype "passive"))
    )
    (net (code "48") (name "/VDD22DCDC") (class "Default")
      (node (ref "J1") (pin "19") (pinfunction "19_19") (pintype "bidirectional"))
      (node (ref "R56") (pin "2") (pinfunction "2_2") (pintype "passive"))
    )
    (net (code "49") (name "/VDD22LDO_FB") (class "Default")
      (node (ref "C10") (pin "1") (pinfunction "1_1") (pintype "passive"))
      (node (ref "C11") (pin "2") (pinfunction "2_2") (pintype "passive"))
      (node (ref "C15") (pin "2") (pinfunction "2_2") (pintype "passive"))
      (node (ref "J26") (pin "6") (pinfunction "6_6") (pintype "bidirectional"))
      (node (ref "L1") (pin "2") (pinfunction "2_2") (pintype "passive"))
      (node (ref "L3") (pin "1") (pinfunction "1_1") (pintype "passive"))
      (node (ref "R57") (pin "1") (pinfunction "1_1") (pintype "passive"))
      (node (ref "U1") (pin "64") (pinfunction "VDD22LDO_FB_64") (pintype "passive"))
      (node (ref "U1") (pin "70") (pinfunction "VDD22MCUI_70") (pintype "passive"))
    )
    (net (code "50") (name "/VDD22_RFI") (class "Default")
      (node (ref "C23") (pin "1") (pinfunction "1_1") (pintype "passive"))
      (node (ref "J26") (pin "2") (pinfunction "2_2") (pintype "bidirectional"))
      (node (ref "L3") (pin "2") (pinfunction "2_2") (pintype "passive"))
      (node (ref "R58") (pin "1") (pinfunction "1_1") (pintype "passive"))
      (node (ref "U1") (pin "15") (pinfunction "VDD22_RFI_15") (pintype "passive"))
    )
    (net (code "51") (name "/VDDH43") (class "Default")
      (node (ref "C12") (pin "1") (pinfunction "1_1") (pintype "passive"))
      (node (ref "C63") (pin "2") (pinfunction "2_2") (pintype "passive"))
      (node (ref "J26") (pin "17") (pinfunction "17_17") (pintype "bidirectional"))
      (node (ref "J26") (pin "19") (pinfunction "19_19") (pintype "bidirectional"))
      (node (ref "U1") (pin "59") (pinfunction "VDDH43_RTC_59") (pintype "passive"))
      (node (ref "U1") (pin "67") (pinfunction "VDDH43_67") (pintype "passive"))
    )
    (net (code "52") (name "/WKUP") (class "Default")
      (node (ref "R24") (pin "1") (pinfunction "1_1") (pintype "passive"))
      (node (ref "U1") (pin "60") (pinfunction "WKUP_60") (pintype "passive"))
    )
    (net (code "53") (name "/XTAL_HFn") (class "Default")
      (node (ref "C24") (pin "2") (pinfunction "2_2") (pintype "passive"))
      (node (ref "C25") (pin "1") (pinfunction "1_1") (pintype "passive"))
      (node (ref "U1") (pin "32") (pinfunction "XTAL_HFn_32") (pintype "passive"))
    )
    (net (code "54") (name "GND") (class "Default")
      (node (ref "C10") (pin "2") (pinfunction "2_2") (pintype "passive"))
      (node (ref "C11") (pin "1") (pinfunction "1_1") (pintype "passive"))
      (node (ref "C12") (pin "2") (pinfunction "2_2") (pintype "passive"))
      (node (ref "C13") (pin "2") (pinfunction "2_2") (pintype "passive"))
      (node (ref "C14") (pin "2") (pinfunction "2_2") (pintype "passive"))
      (node (ref "C15") (pin "1") (pinfunction "1_1") (pintype "passive"))
      (node (ref "C17") (pin "1") (pinfunction "1_1") (pintype "passive"))
      (node (ref "C18") (pin "2") (pinfunction "2_2") (pintype "passive"))
      (node (ref "C19") (pin "2") (pinfunction "2_2") (pintype "passive"))
      (node (ref "C20") (pin "1") (pinfunction "1_1") (pintype "passive"))
      (node (ref "C21") (pin "1") (pinfunction "1_1") (pintype "passive"))
      (node (ref "C22") (pin "1") (pinfunction "1_1") (pintype "passive"))
      (node (ref "C23") (pin "2") (pinfunction "2_2") (pintype "passive"))
      (node (ref "C25") (pin "2") (pinfunction "2_2") (pintype "passive"))
      (node (ref "C26") (pin "1") (pinfunction "1_1") (pintype "passive"))
      (node (ref "C28") (pin "1") (pinfunction "1_1") (pintype "passive"))
      (node (ref "C29") (pin "1") (pinfunction "1_1") (pintype "passive"))
      (node (ref "C30") (pin "1") (pinfunction "1_1") (pintype "passive"))
      (node (ref "C31") (pin "1") (pinfunction "1_1") (pintype "passive"))
      (node (ref "C32") (pin "1") (pinfunction "1_1") (pintype "passive"))
      (node (ref "C63") (pin "1") (pinfunction "1_1") (pintype "passive"))
      (node (ref "C65") (pin "1") (pinfunction "1_1") (pintype "passive"))
      (node (ref "C9") (pin "2") (pinfunction "2_2") (pintype "passive"))
      (node (ref "J1") (pin "10") (pinfunction "10_10") (pintype "bidirectional"))
      (node (ref "J1") (pin "17") (pinfunction "17_17") (pintype "bidirectional"))
      (node (ref "J1") (pin "20") (pinfunction "20_20") (pintype "bidirectional"))
      (node (ref "J26") (pin "13") (pinfunction "13_13") (pintype "bidirectional"))
      (node (ref "J26") (pin "20") (pinfunction "20_20") (pintype "bidirectional"))
      (node (ref "J26") (pin "9") (pinfunction "9_9") (pintype "bidirectional"))
      (node (ref "J27") (pin "16") (pinfunction "16_16") (pintype "bidirectional"))
      (node (ref "J27") (pin "17") (pinfunction "17_17") (pintype "bidirectional"))
      (node (ref "J27") (pin "20") (pinfunction "20_20") (pintype "bidirectional"))
      (node (ref "J27") (pin "3") (pinfunction "3_3") (pintype "bidirectional"))
      (node (ref "J28") (pin "2") (pinfunction "2_2") (pintype "bidirectional"))
      (node (ref "J29") (pin "2") (pinfunction "2_2") (pintype "bidirectional"))
      (node (ref "J30") (pin "2") (pinfunction "2_2") (pintype "bidirectional"))
      (node (ref "J31") (pin "2") (pinfunction "2_2") (pintype "bidirectional"))
      (node (ref "J32") (pin "2") (pinfunction "2_2") (pintype "bidirectional"))
      (node (ref "R23") (pin "2") (pinfunction "2_2") (pintype "passive"))
      (node (ref "R24") (pin "2") (pinfunction "2_2") (pintype "passive"))
      (node (ref "R25") (pin "1") (pinfunction "1_1") (pintype "passive"))
      (node (ref "R26") (pin "2") (pinfunction "2_2") (pintype "passive"))
      (node (ref "R55") (pin "2") (pinfunction "2_2") (pintype "passive"))
      (node (ref "U1") (pin "16") (pinfunction "GND_RF_16") (pintype "passive"))
      (node (ref "U1") (pin "18") (pinfunction "GND_RF_18") (pintype "passive"))
      (node (ref "U1") (pin "20") (pinfunction "GND_RF_20") (pintype "passive"))
      (node (ref "U1") (pin "21") (pinfunction "GND_RF_21") (pintype "passive"))
      (node (ref "U1") (pin "24") (pinfunction "GND_RF_24") (pintype "passive"))
      (node (ref "U1") (pin "26") (pinfunction "GND_RF_26") (pintype "passive"))
      (node (ref "U1") (pin "28") (pinfunction "GND_RF_28") (pintype "passive"))
      (node (ref "U1") (pin "54") (pinfunction "GND_MCU_54") (pintype "passive"))
      (node (ref "U1") (pin "57") (pinfunction "GND_MCU_57") (pintype "passive"))
      (node (ref "U1") (pin "89") (pinfunction "GND_89") (pintype "passive"))
    )
    (net (code "55") (name "Net-(U1-GPIO26)") (class "Default")
      (node (ref "R62") (pin "1") (pinfunction "1_1") (pintype "passive"))
      (node (ref "U1") (pin "46") (pinfunction "GPIO26_46") (pintype "passive"))
    )
    (net (code "56") (name "Net-(U1-GPIO27)") (class "Default")
      (node (ref "R61") (pin "1") (pinfunction "1_1") (pintype "passive"))
      (node (ref "U1") (pin "47") (pinfunction "GPIO27_47") (pintype "passive"))
    )
    (net (code "57") (name "Net-(U1-GPIO28)") (class "Default")
      (node (ref "R60") (pin "1") (pinfunction "1_1") (pintype "passive"))
      (node (ref "U1") (pin "48") (pinfunction "GPIO28_48") (pintype "passive"))
    )
    (net (code "58") (name "Net-(U1-GPIO29)") (class "Default")
      (node (ref "R59") (pin "1") (pinfunction "1_1") (pintype "passive"))
      (node (ref "U1") (pin "49") (pinfunction "GPIO29_49") (pintype "passive"))
    )
    (net (code "59") (name "Net-(U1-VDD18GO)") (class "Default")
      (node (ref "C20") (pin "2") (pinfunction "2_2") (pintype "passive"))
      (node (ref "R27") (pin "1") (pinfunction "1_1") (pintype "passive"))
      (node (ref "R53") (pin "1") (pinfunction "1_1") (pintype "passive"))
      (node (ref "U1") (pin "68") (pinfunction "VDD18GO_68") (pintype "passive"))
    )
    (net (code "60") (name "Net-(U1-VDD22DCDC)") (class "Default")
      (node (ref "L1") (pin "1") (pinfunction "1_1") (pintype "passive"))
      (node (ref "R56") (pin "1") (pinfunction "1_1") (pintype "passive"))
      (node (ref "U1") (pin "65") (pinfunction "VDD22DCDC_65") (pintype "passive"))
    )
    (net (code "61") (name "Net-(U1-XTAL_32Kn)") (class "Default")
      (node (ref "C16") (pin "2") (pinfunction "2_2") (pintype "passive"))
      (node (ref "U1") (pin "55") (pinfunction "XTAL_32Kn_55") (pintype "passive"))
    )
    (net (code "62") (name "unconnected-(J1-Pad3)") (class "Default")
      (node (ref "J1") (pin "3") (pinfunction "3_3") (pintype "bidirectional"))
    )
    (net (code "63") (name "unconnected-(J1-Pad5)") (class "Default")
      (node (ref "J1") (pin "5") (pinfunction "5_5") (pintype "bidirectional"))
    )
    (net (code "64") (name "unconnected-(J26-Pad1)") (class "Default")
      (node (ref "J26") (pin "1") (pinfunction "1_1") (pintype "bidirectional"))
    )
    (net (code "65") (name "unconnected-(J26-Pad7)") (class "Default")
      (node (ref "J26") (pin "7") (pinfunction "7_7") (pintype "bidirectional"))
    )
    (net (code "66") (name "unconnected-(J27-Pad1)") (class "Default")
      (node (ref "J27") (pin "1") (pinfunction "1_1") (pintype "bidirectional"))
    )
    (net (code "67") (name "unconnected-(U1-GPIO0-Pad83)") (class "Default")
      (node (ref "U1") (pin "83") (pinfunction "GPIO0_83") (pintype "passive"))
    )
    (net (code "68") (name "unconnected-(U1-GPIO1-Pad84)") (class "Default")
      (node (ref "U1") (pin "84") (pinfunction "GPIO1_84") (pintype "passive"))
    )
    (net (code "69") (name "unconnected-(U1-GPIO2-Pad85)") (class "Default")
      (node (ref "U1") (pin "85") (pinfunction "GPIO2_85") (pintype "passive"))
    )
    (net (code "70") (name "unconnected-(U1-GPIO3-Pad86)") (class "Default")
      (node (ref "U1") (pin "86") (pinfunction "GPIO3_86") (pintype "passive"))
    )
    (net (code "71") (name "unconnected-(U1-GPIO4-Pad87)") (class "Default")
      (node (ref "U1") (pin "87") (pinfunction "GPIO4_87") (pintype "passive"))
    )
    (net (code "72") (name "unconnected-(U1-GPIO5-Pad88)") (class "Default")
      (node (ref "U1") (pin "88") (pinfunction "GPIO5_88") (pintype "passive"))
    )
    (net (code "73") (name "unconnected-(U1-GPIO6-Pad2)") (class "Default")
      (node (ref "U1") (pin "2") (pinfunction "GPIO6_2") (pintype "passive"))
    )
    (net (code "74") (name "unconnected-(U1-GPIO7-Pad3)") (class "Default")
      (node (ref "U1") (pin "3") (pinfunction "GPIO7_3") (pintype "passive"))
    )
    (net (code "75") (name "unconnected-(U1-GPIO8-Pad4)") (class "Default")
      (node (ref "U1") (pin "4") (pinfunction "GPIO8_4") (pintype "passive"))
    )
    (net (code "76") (name "unconnected-(U1-GPIO9-Pad5)") (class "Default")
      (node (ref "U1") (pin "5") (pinfunction "GPIO9_5") (pintype "passive"))
    )
    (net (code "77") (name "unconnected-(U1-GPIO10-Pad6)") (class "Default")
      (node (ref "U1") (pin "6") (pinfunction "GPIO10_6") (pintype "passive"))
    )
    (net (code "78") (name "unconnected-(U1-GPIO11-Pad7)") (class "Default")
      (node (ref "U1") (pin "7") (pinfunction "GPIO11_7") (pintype "passive"))
    )
    (net (code "79") (name "unconnected-(U1-GPIO12-Pad9)") (class "Default")
      (node (ref "U1") (pin "9") (pinfunction "GPIO12_9") (pintype "passive"))
    )
    (net (code "80") (name "unconnected-(U1-GPIO13-Pad10)") (class "Default")
      (node (ref "U1") (pin "10") (pinfunction "GPIO13_10") (pintype "passive"))
    )
    (net (code "81") (name "unconnected-(U1-GPIO14-Pad11)") (class "Default")
      (node (ref "U1") (pin "11") (pinfunction "GPIO14_11") (pintype "passive"))
    )
    (net (code "82") (name "unconnected-(U1-GPIO15-Pad12)") (class "Default")
      (node (ref "U1") (pin "12") (pinfunction "GPIO15_12") (pintype "passive"))
    )
    (net (code "83") (name "unconnected-(U1-GPIO16-Pad35)") (class "Default")
      (node (ref "U1") (pin "35") (pinfunction "GPIO16_35") (pintype "passive"))
    )
    (net (code "84") (name "unconnected-(U1-GPIO17-Pad36)") (class "Default")
      (node (ref "U1") (pin "36") (pinfunction "GPIO17_36") (pintype "passive"))
    )
    (net (code "85") (name "unconnected-(U1-GPIO18-Pad37)") (class "Default")
      (node (ref "U1") (pin "37") (pinfunction "GPIO18_37") (pintype "passive"))
    )
    (net (code "86") (name "unconnected-(U1-GPIO19-Pad38)") (class "Default")
      (node (ref "U1") (pin "38") (pinfunction "GPIO19_38") (pintype "passive"))
    )
    (net (code "87") (name "unconnected-(U1-GPIO20-Pad39)") (class "Default")
      (node (ref "U1") (pin "39") (pinfunction "GPIO20_39") (pintype "passive"))
    )
    (net (code "88") (name "unconnected-(U1-GPIO21-Pad40)") (class "Default")
      (node (ref "U1") (pin "40") (pinfunction "GPIO21_40") (pintype "passive"))
    )
    (net (code "89") (name "unconnected-(U1-GPIO22-Pad41)") (class "Default")
      (node (ref "U1") (pin "41") (pinfunction "GPIO22_41") (pintype "passive"))
    )
    (net (code "90") (name "unconnected-(U1-GPIO23-Pad42)") (class "Default")
      (node (ref "U1") (pin "42") (pinfunction "GPIO23_42") (pintype "passive"))
    )
    (net (code "91") (name "unconnected-(U1-GPIO30-Pad50)") (class "Default")
      (node (ref "U1") (pin "50") (pinfunction "GPIO30_50") (pintype "passive"))
    )
    (net (code "92") (name "unconnected-(U1-GPIO31-Pad51)") (class "Default")
      (node (ref "U1") (pin "51") (pinfunction "GPIO31_51") (pintype "passive"))
    )
    (net (code "93") (name "unconnected-(U1-SHDN-Pad61)") (class "Default")
      (node (ref "U1") (pin "61") (pinfunction "SHDN_61") (pintype "passive"))
    )
    (net (code "94") (name "unconnected-(U1-XTAL_32Kp-Pad56)") (class "Default")
      (node (ref "U1") (pin "56") (pinfunction "XTAL_32Kp_56") (pintype "passive"))
    )
    (net (code "95") (name "unconnected-(U1-XTAL_HFp-Pad33)") (class "Default")
      (node (ref "U1") (pin "33") (pinfunction "XTAL_HFp_33") (pintype "passive"))
    )
  )
)
